# EEPROM_ID.net
KiCad netlist of a schematic drawn in Altium Designer
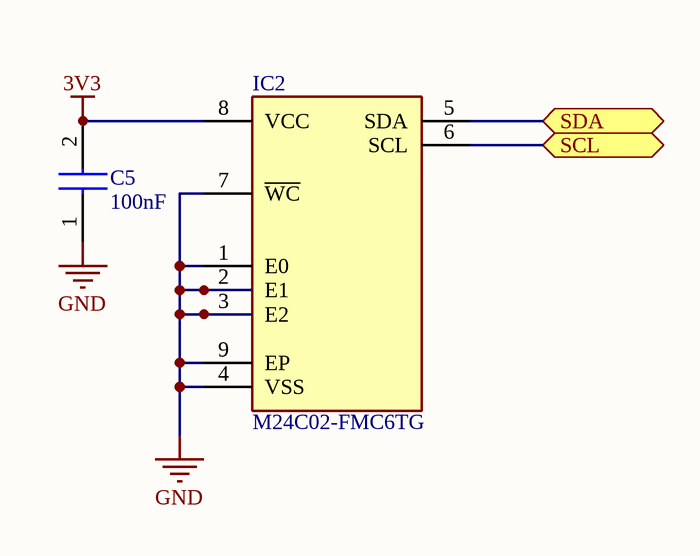
[diagram p0: EEPROM_ID.SchDoc]

(export (version "E")
  (design (tool "Eeschema 10.0.6"))
  (components
    (comp (ref "C5")
      (value "100nF")
      (footprint "SamacSys:CAPC1005X70N")
      (description "Capacitor")
      (fields
        (field (name "MANUFACTURER_PART_NUMBER") "GRM155R61A104KA01D")
        (field (name "MOUSER PART NUMBER") "81-GRM155R61A104KA01")
      )
      (libsource (lib "*") (part "GRM155R61A104KA01D"))
    )
    (comp (ref "IC2")
      (value "M24C02-FMC6TG")
      (footprint "SamacSys:M24C02FMC6TG")
      (description "Integrated Circuit")
      (fields (field (name "MOUSER PART NUMBER") "511-M24C02-FMC6TG"))
      (libsource (lib "SamacSys") (part "M24C02-FMC6TG"))
    )
  )
  (nets
    (net (code "1") (name "/SCL") (class "Default")
      (node (ref "IC2") (pin "6") (pinfunction "SCL_6") (pintype "passive"))
    )
    (net (code "2") (name "/SDA") (class "Default")
      (node (ref "IC2") (pin "5") (pinfunction "SDA_5") (pintype "passive"))
    )
    (net (code "3") (name "3V3") (class "Default")
      (node (ref "C5") (pin "2") (pinfunction "2_2") (pintype "passive"))
      (node (ref "IC2") (pin "8") (pinfunction "VCC_8") (pintype "passive"))
    )
    (net (code "4") (name "GND") (class "Default")
      (node (ref "C5") (pin "1") (pinfunction "1_1") (pintype "passive"))
      (node (ref "IC2") (pin "1") (pinfunction "E0_1") (pintype "passive"))
      (node (ref "IC2") (pin "2") (pinfunction "E1_2") (pintype "passive"))
      (node (ref "IC2") (pin "3") (pinfunction "E2_3") (pintype "passive"))
      (node (ref "IC2") (pin "4") (pinfunction "VSS_4") (pintype "passive"))
      (node (ref "IC2") (pin "7") (pinfunction "~{WC}_7") (pintype "passive"))
      (node (ref "IC2") (pin "9") (pinfunction "EP_9") (pintype "passive"))
    )
  )
)
